# sot23-5-op-amp-proto__TOP_LEVEL__A.net
KiCad netlist of a schematic drawn in Altium Designer
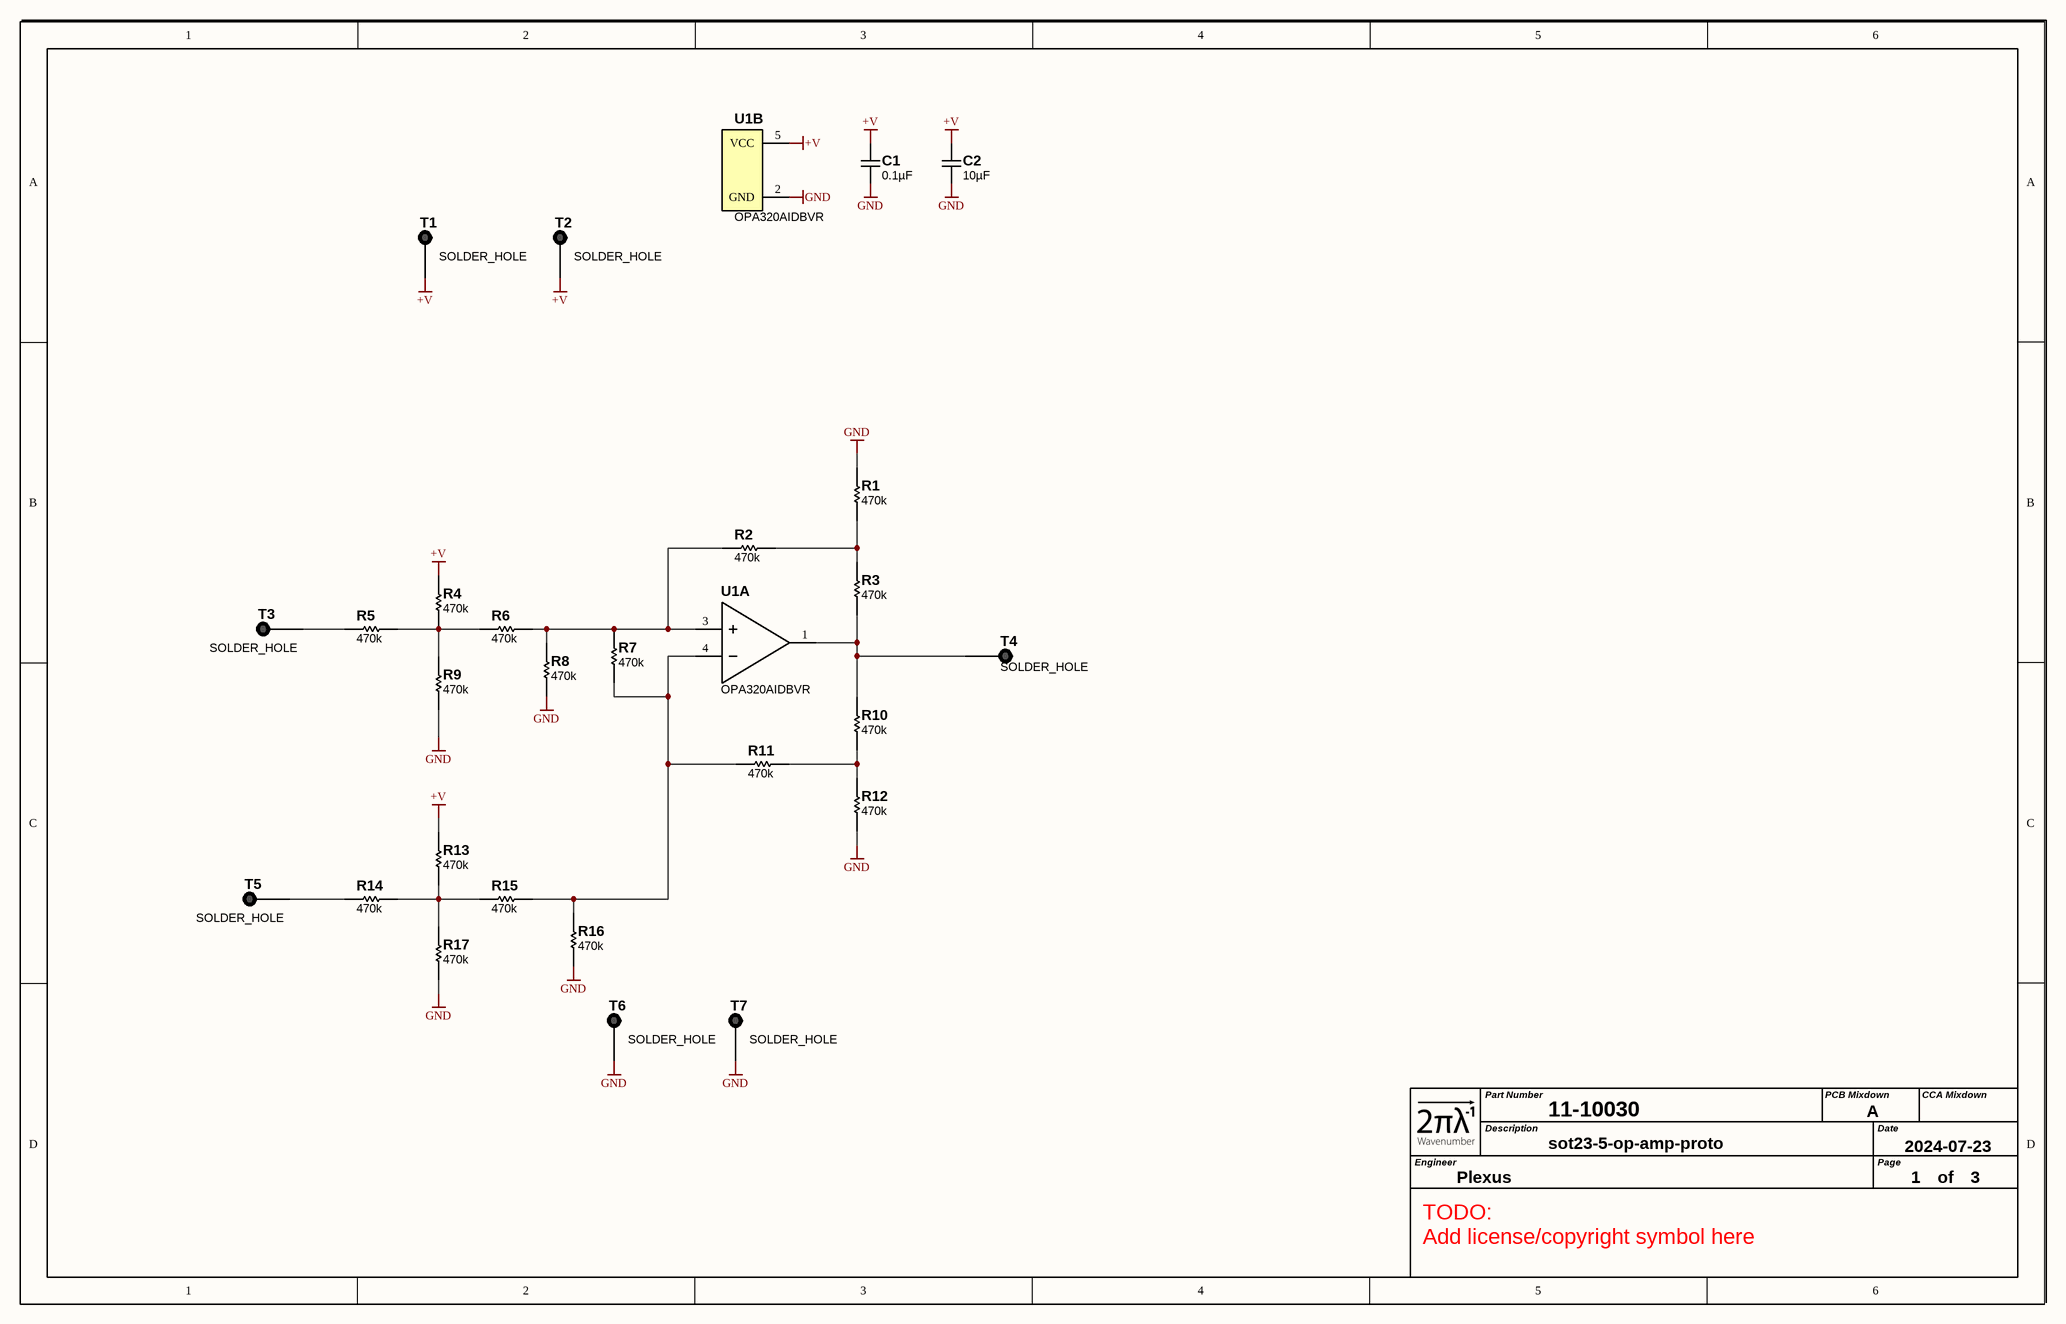
[diagram p0: sot23-5-op-amp-proto__TOP_LEVEL__A.SchDoc]

(export (version "E")
  (design (tool "Eeschema 10.0.6"))
  (components
    (comp (ref "C1")
      (value "0.1µF")
      (footprint "C0603_0.90MM_MD")
      (description "CAP CER 0.1UF 16V X7R 0603")
      (fields
        (field (name "MANUFACTURER PART NUMBER") "GCJ188R71C104KA01D")
        (field (name "MANUFACTURER") "Murata Electronics")
      )
      (libsource (lib "Capacitors - Murata - AEC-Q200") (part "C_2P_NP"))
    )
    (comp (ref "C2")
      (value "10µF")
      (footprint "C0805_1.40MM_MD")
      (description "CAP CER 10UF 10V X7R 0805")
      (fields
        (field (name "MANUFACTURER PART NUMBER") "GCM21BR71A106KE22K")
        (field (name "MANUFACTURER") "Murata Electronics")
      )
      (libsource (lib "Capacitors - Murata - AEC-Q200") (part "C_2P_NP"))
    )
    (comp (ref "R1")
      (value "470k")
      (footprint "R0603_0.55MM_MD")
      (description "RES 470K OHM 1/10W 1% 0603 SMD")
      (fields
        (field (name "MANUFACTURER PART NUMBER") "ERJ-3EKF4703V")
        (field (name "MANUFACTURER") "Panasonic Electronic Components")
      )
      (libsource (lib "Resistors - Panasonic - AEC-Q200") (part "R_2P"))
    )
    (comp (ref "R2")
      (value "470k")
      (footprint "R0603_0.55MM_MD")
      (description "RES 470K OHM 1/10W 1% 0603 SMD")
      (fields
        (field (name "MANUFACTURER PART NUMBER") "ERJ-3EKF4703V")
        (field (name "MANUFACTURER") "Panasonic Electronic Components")
      )
      (libsource (lib "Resistors - Panasonic - AEC-Q200") (part "R_2P"))
    )
    (comp (ref "R3")
      (value "470k")
      (footprint "R0603_0.55MM_MD")
      (description "RES 470K OHM 1/10W 1% 0603 SMD")
      (fields
        (field (name "MANUFACTURER PART NUMBER") "ERJ-3EKF4703V")
        (field (name "MANUFACTURER") "Panasonic Electronic Components")
      )
      (libsource (lib "Resistors - Panasonic - AEC-Q200") (part "R_2P"))
    )
    (comp (ref "R4")
      (value "470k")
      (footprint "R0603_0.55MM_MD")
      (description "RES 470K OHM 1/10W 1% 0603 SMD")
      (fields
        (field (name "MANUFACTURER PART NUMBER") "ERJ-3EKF4703V")
        (field (name "MANUFACTURER") "Panasonic Electronic Components")
      )
      (libsource (lib "Resistors - Panasonic - AEC-Q200") (part "R_2P"))
    )
    (comp (ref "R5")
      (value "470k")
      (footprint "R0603_0.55MM_MD")
      (description "RES 470K OHM 1/10W 1% 0603 SMD")
      (fields
        (field (name "MANUFACTURER PART NUMBER") "ERJ-3EKF4703V")
        (field (name "MANUFACTURER") "Panasonic Electronic Components")
      )
      (libsource (lib "Resistors - Panasonic - AEC-Q200") (part "R_2P"))
    )
    (comp (ref "R6")
      (value "470k")
      (footprint "R0603_0.55MM_MD")
      (description "RES 470K OHM 1/10W 1% 0603 SMD")
      (fields
        (field (name "MANUFACTURER PART NUMBER") "ERJ-3EKF4703V")
        (field (name "MANUFACTURER") "Panasonic Electronic Components")
      )
      (libsource (lib "Resistors - Panasonic - AEC-Q200") (part "R_2P"))
    )
    (comp (ref "R7")
      (value "470k")
      (footprint "R0603_0.55MM_MD")
      (description "RES 470K OHM 1/10W 1% 0603 SMD")
      (fields
        (field (name "MANUFACTURER PART NUMBER") "ERJ-3EKF4703V")
        (field (name "MANUFACTURER") "Panasonic Electronic Components")
      )
      (libsource (lib "Resistors - Panasonic - AEC-Q200") (part "R_2P"))
    )
    (comp (ref "R8")
      (value "470k")
      (footprint "R0603_0.55MM_MD")
      (description "RES 470K OHM 1/10W 1% 0603 SMD")
      (fields
        (field (name "MANUFACTURER PART NUMBER") "ERJ-3EKF4703V")
        (field (name "MANUFACTURER") "Panasonic Electronic Components")
      )
      (libsource (lib "Resistors - Panasonic - AEC-Q200") (part "R_2P"))
    )
    (comp (ref "R9")
      (value "470k")
      (footprint "R0603_0.55MM_MD")
      (description "RES 470K OHM 1/10W 1% 0603 SMD")
      (fields
        (field (name "MANUFACTURER PART NUMBER") "ERJ-3EKF4703V")
        (field (name "MANUFACTURER") "Panasonic Electronic Components")
      )
      (libsource (lib "Resistors - Panasonic - AEC-Q200") (part "R_2P"))
    )
    (comp (ref "R10")
      (value "470k")
      (footprint "R0603_0.55MM_MD")
      (description "RES 470K OHM 1/10W 1% 0603 SMD")
      (fields
        (field (name "MANUFACTURER PART NUMBER") "ERJ-3EKF4703V")
        (field (name "MANUFACTURER") "Panasonic Electronic Components")
      )
      (libsource (lib "Resistors - Panasonic - AEC-Q200") (part "R_2P"))
    )
    (comp (ref "R11")
      (value "470k")
      (footprint "R0603_0.55MM_MD")
      (description "RES 470K OHM 1/10W 1% 0603 SMD")
      (fields
        (field (name "MANUFACTURER PART NUMBER") "ERJ-3EKF4703V")
        (field (name "MANUFACTURER") "Panasonic Electronic Components")
      )
      (libsource (lib "Resistors - Panasonic - AEC-Q200") (part "R_2P"))
    )
    (comp (ref "R12")
      (value "470k")
      (footprint "R0603_0.55MM_MD")
      (description "RES 470K OHM 1/10W 1% 0603 SMD")
      (fields
        (field (name "MANUFACTURER PART NUMBER") "ERJ-3EKF4703V")
        (field (name "MANUFACTURER") "Panasonic Electronic Components")
      )
      (libsource (lib "Resistors - Panasonic - AEC-Q200") (part "R_2P"))
    )
    (comp (ref "R13")
      (value "470k")
      (footprint "R0603_0.55MM_MD")
      (description "RES 470K OHM 1/10W 1% 0603 SMD")
      (fields
        (field (name "MANUFACTURER PART NUMBER") "ERJ-3EKF4703V")
        (field (name "MANUFACTURER") "Panasonic Electronic Components")
      )
      (libsource (lib "Resistors - Panasonic - AEC-Q200") (part "R_2P"))
    )
    (comp (ref "R14")
      (value "470k")
      (footprint "R0603_0.55MM_MD")
      (description "RES 470K OHM 1/10W 1% 0603 SMD")
      (fields
        (field (name "MANUFACTURER PART NUMBER") "ERJ-3EKF4703V")
        (field (name "MANUFACTURER") "Panasonic Electronic Components")
      )
      (libsource (lib "Resistors - Panasonic - AEC-Q200") (part "R_2P"))
    )
    (comp (ref "R15")
      (value "470k")
      (footprint "R0603_0.55MM_MD")
      (description "RES 470K OHM 1/10W 1% 0603 SMD")
      (fields
        (field (name "MANUFACTURER PART NUMBER") "ERJ-3EKF4703V")
        (field (name "MANUFACTURER") "Panasonic Electronic Components")
      )
      (libsource (lib "Resistors - Panasonic - AEC-Q200") (part "R_2P"))
    )
    (comp (ref "R16")
      (value "470k")
      (footprint "R0603_0.55MM_MD")
      (description "RES 470K OHM 1/10W 1% 0603 SMD")
      (fields
        (field (name "MANUFACTURER PART NUMBER") "ERJ-3EKF4703V")
        (field (name "MANUFACTURER") "Panasonic Electronic Components")
      )
      (libsource (lib "Resistors - Panasonic - AEC-Q200") (part "R_2P"))
    )
    (comp (ref "R17")
      (value "470k")
      (footprint "R0603_0.55MM_MD")
      (description "RES 470K OHM 1/10W 1% 0603 SMD")
      (fields
        (field (name "MANUFACTURER PART NUMBER") "ERJ-3EKF4703V")
        (field (name "MANUFACTURER") "Panasonic Electronic Components")
      )
      (libsource (lib "Resistors - Panasonic - AEC-Q200") (part "R_2P"))
    )
    (comp (ref "T1")
      (value "SOLDER_HOLE")
      (footprint "SOLDER_HOLE -  22AWG")
      (description "A Generic Hole for attaching flying leads")
      (libsource (lib "wn__Connector__wire_to_board") (part "SOLDER_HOLE"))
    )
    (comp (ref "T2")
      (value "SOLDER_HOLE")
      (footprint "SOLDER_HOLE -  22AWG")
      (description "A Generic Hole for attaching flying leads")
      (libsource (lib "wn__Connector__wire_to_board") (part "SOLDER_HOLE"))
    )
    (comp (ref "T3")
      (value "SOLDER_HOLE")
      (footprint "SOLDER_HOLE -  24AWG")
      (description "A Generic Hole for attaching flying leads")
      (libsource (lib "wn__Connector__wire_to_board") (part "SOLDER_HOLE"))
    )
    (comp (ref "T4")
      (value "SOLDER_HOLE")
      (footprint "SOLDER_HOLE -  22AWG")
      (description "A Generic Hole for attaching flying leads")
      (libsource (lib "wn__Connector__wire_to_board") (part "SOLDER_HOLE"))
    )
    (comp (ref "T5")
      (value "SOLDER_HOLE")
      (footprint "SOLDER_HOLE -  24AWG")
      (description "A Generic Hole for attaching flying leads")
      (libsource (lib "wn__Connector__wire_to_board") (part "SOLDER_HOLE"))
    )
    (comp (ref "T6")
      (value "SOLDER_HOLE")
      (footprint "SOLDER_HOLE -  22AWG")
      (description "A Generic Hole for attaching flying leads")
      (libsource (lib "wn__Connector__wire_to_board") (part "SOLDER_HOLE"))
    )
    (comp (ref "T7")
      (value "SOLDER_HOLE")
      (footprint "SOLDER_HOLE -  22AWG")
      (description "A Generic Hole for attaching flying leads")
      (libsource (lib "wn__Connector__wire_to_board") (part "SOLDER_HOLE"))
    )
    (comp (ref "U1")
      (value "OPA320AIDBVR")
      (footprint "SOT23-5")
      (description "IC OPAMP GP 20MHZ RRO SOT23-5")
      (fields (field (name "MANUFACTURER") "Texas Instruments"))
      (libsource (lib "wn__OPAMP") (part "OPA320AIDBVR"))
    )
  )
  (nets
    (net (code "1") (name "+V") (class "Default")
      (node (ref "C1") (pin "2") (pinfunction "1_2") (pintype "passive"))
      (node (ref "C2") (pin "2") (pinfunction "1_2") (pintype "passive"))
      (node (ref "R13") (pin "2") (pinfunction "2_2") (pintype "passive"))
      (node (ref "R4") (pin "2") (pinfunction "2_2") (pintype "passive"))
      (node (ref "T1") (pin "1") (pinfunction "1_1") (pintype "passive"))
      (node (ref "T2") (pin "1") (pinfunction "1_1") (pintype "passive"))
      (node (ref "U1") (pin "5") (pinfunction "VCC_5") (pintype "passive"))
    )
    (net (code "2") (name "GND") (class "Default")
      (node (ref "C1") (pin "1") (pinfunction "1_1") (pintype "passive"))
      (node (ref "C2") (pin "1") (pinfunction "1_1") (pintype "passive"))
      (node (ref "R1") (pin "2") (pinfunction "2_2") (pintype "passive"))
      (node (ref "R12") (pin "1") (pinfunction "1_1") (pintype "passive"))
      (node (ref "R16") (pin "1") (pinfunction "1_1") (pintype "passive"))
      (node (ref "R17") (pin "1") (pinfunction "1_1") (pintype "passive"))
      (node (ref "R8") (pin "1") (pinfunction "1_1") (pintype "passive"))
      (node (ref "R9") (pin "1") (pinfunction "1_1") (pintype "passive"))
      (node (ref "T6") (pin "1") (pinfunction "1_1") (pintype "passive"))
      (node (ref "T7") (pin "1") (pinfunction "1_1") (pintype "passive"))
      (node (ref "U1") (pin "2") (pinfunction "GND_2") (pintype "passive"))
    )
    (net (code "3") (name "Net-(R1-Pad1)") (class "Default")
      (node (ref "R1") (pin "1") (pinfunction "1_1") (pintype "passive"))
      (node (ref "R2") (pin "1") (pinfunction "1_1") (pintype "passive"))
      (node (ref "R3") (pin "2") (pinfunction "2_2") (pintype "passive"))
    )
    (net (code "4") (name "Net-(R4-Pad1)") (class "Default")
      (node (ref "R4") (pin "1") (pinfunction "1_1") (pintype "passive"))
      (node (ref "R5") (pin "1") (pinfunction "1_1") (pintype "passive"))
      (node (ref "R6") (pin "2") (pinfunction "2_2") (pintype "passive"))
      (node (ref "R9") (pin "2") (pinfunction "2_2") (pintype "passive"))
    )
    (net (code "5") (name "Net-(R5-Pad2)") (class "Default")
      (node (ref "R5") (pin "2") (pinfunction "2_2") (pintype "passive"))
      (node (ref "T3") (pin "1") (pinfunction "1_1") (pintype "passive"))
    )
    (net (code "6") (name "Net-(R10-Pad1)") (class "Default")
      (node (ref "R10") (pin "1") (pinfunction "1_1") (pintype "passive"))
      (node (ref "R11") (pin "1") (pinfunction "1_1") (pintype "passive"))
      (node (ref "R12") (pin "2") (pinfunction "2_2") (pintype "passive"))
    )
    (net (code "7") (name "Net-(R13-Pad1)") (class "Default")
      (node (ref "R13") (pin "1") (pinfunction "1_1") (pintype "passive"))
      (node (ref "R14") (pin "1") (pinfunction "1_1") (pintype "passive"))
      (node (ref "R15") (pin "2") (pinfunction "2_2") (pintype "passive"))
      (node (ref "R17") (pin "2") (pinfunction "2_2") (pintype "passive"))
    )
    (net (code "8") (name "Net-(R14-Pad2)") (class "Default")
      (node (ref "R14") (pin "2") (pinfunction "2_2") (pintype "passive"))
      (node (ref "T5") (pin "1") (pinfunction "1_1") (pintype "passive"))
    )
    (net (code "9") (name "Net-(U1A-+)") (class "Default")
      (node (ref "R2") (pin "2") (pinfunction "2_2") (pintype "passive"))
      (node (ref "R6") (pin "1") (pinfunction "1_1") (pintype "passive"))
      (node (ref "R7") (pin "2") (pinfunction "2_2") (pintype "passive"))
      (node (ref "R8") (pin "2") (pinfunction "2_2") (pintype "passive"))
      (node (ref "U1") (pin "3") (pinfunction "+_3") (pintype "passive"))
    )
    (net (code "10") (name "Net-(U1A--)") (class "Default")
      (node (ref "R11") (pin "2") (pinfunction "2_2") (pintype "passive"))
      (node (ref "R15") (pin "1") (pinfunction "1_1") (pintype "passive"))
      (node (ref "R16") (pin "2") (pinfunction "2_2") (pintype "passive"))
      (node (ref "R7") (pin "1") (pinfunction "1_1") (pintype "passive"))
      (node (ref "U1") (pin "4") (pinfunction "-_4") (pintype "passive"))
    )
    (net (code "11") (name "Net-(U1A-OUT)") (class "Default")
      (node (ref "R10") (pin "2") (pinfunction "2_2") (pintype "passive"))
      (node (ref "R3") (pin "1") (pinfunction "1_1") (pintype "passive"))
      (node (ref "T4") (pin "1") (pinfunction "1_1") (pintype "passive"))
      (node (ref "U1") (pin "1") (pinfunction "OUT_1") (pintype "passive"))
    )
  )
)
